# CPU.net
KiCad netlist of a schematic drawn in Altium Designer
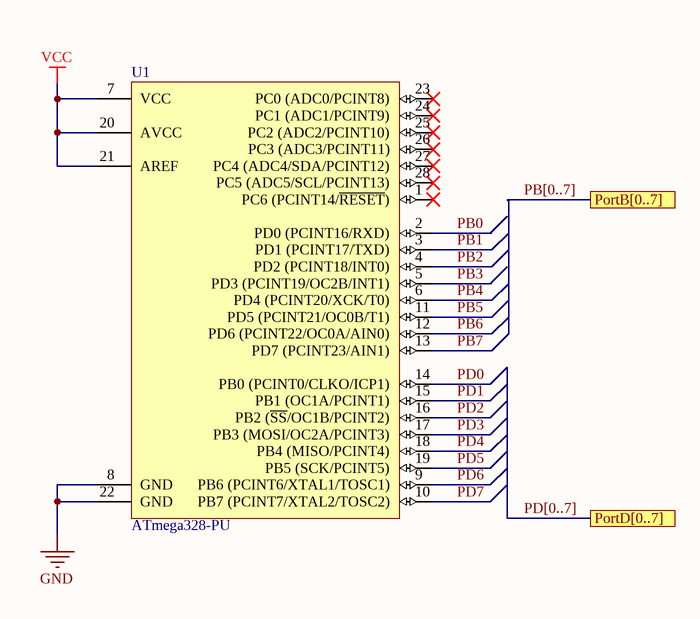
[diagram p0: CPU.SchDoc]

(export (version "E")
  (design (tool "Eeschema 10.0.6"))
  (components
    (comp (ref "U1")
      (value "ATmega328-PU")
      (footprint "28P3")
      (libsource (lib "Altium Content Vault") (part "MC-8B-ATM48-IL28"))
    )
  )
  (nets
    (net (code "1") (name "/PB0") (class "Default")
      (node (ref "U1") (pin "2") (pinfunction "PD0_(PCINT16/RXD)_2") (pintype "bidirectional"))
    )
    (net (code "2") (name "/PB1") (class "Default")
      (node (ref "U1") (pin "3") (pinfunction "PD1_(PCINT17/TXD)_3") (pintype "bidirectional"))
    )
    (net (code "3") (name "/PB2") (class "Default")
      (node (ref "U1") (pin "4") (pinfunction "PD2_(PCINT18/INT0)_4") (pintype "bidirectional"))
    )
    (net (code "4") (name "/PB3") (class "Default")
      (node (ref "U1") (pin "5") (pinfunction "PD3_(PCINT19/OC2B/INT1)_5") (pintype "bidirectional"))
    )
    (net (code "5") (name "/PB4") (class "Default")
      (node (ref "U1") (pin "6") (pinfunction "PD4_(PCINT20/XCK/T0)_6") (pintype "bidirectional"))
    )
    (net (code "6") (name "/PB5") (class "Default")
      (node (ref "U1") (pin "11") (pinfunction "PD5_(PCINT21/OC0B/T1)_11") (pintype "bidirectional"))
    )
    (net (code "7") (name "/PB6") (class "Default")
      (node (ref "U1") (pin "12") (pinfunction "PD6_(PCINT22/OC0A/AIN0)_12") (pintype "bidirectional"))
    )
    (net (code "8") (name "/PB7") (class "Default")
      (node (ref "U1") (pin "13") (pinfunction "PD7_(PCINT23/AIN1)_13") (pintype "bidirectional"))
    )
    (net (code "10") (name "/PD0") (class "Default")
      (node (ref "U1") (pin "14") (pinfunction "PB0_(PCINT0/CLKO/ICP1)_14") (pintype "bidirectional"))
    )
    (net (code "11") (name "/PD1") (class "Default")
      (node (ref "U1") (pin "15") (pinfunction "PB1_(OC1A/PCINT1)_15") (pintype "bidirectional"))
    )
    (net (code "12") (name "/PD2") (class "Default")
      (node (ref "U1") (pin "16") (pinfunction "PB2_(~{SS}/OC1B/PCINT2)_16") (pintype "bidirectional"))
    )
    (net (code "13") (name "/PD3") (class "Default")
      (node (ref "U1") (pin "17") (pinfunction "PB3_(MOSI/OC2A/PCINT3)_17") (pintype "bidirectional"))
    )
    (net (code "14") (name "/PD4") (class "Default")
      (node (ref "U1") (pin "18") (pinfunction "PB4_(MISO/PCINT4)_18") (pintype "bidirectional"))
    )
    (net (code "15") (name "/PD5") (class "Default")
      (node (ref "U1") (pin "19") (pinfunction "PB5_(SCK/PCINT5)_19") (pintype "bidirectional"))
    )
    (net (code "16") (name "/PD6") (class "Default")
      (node (ref "U1") (pin "9") (pinfunction "PB6_(PCINT6/XTAL1/TOSC1)_9") (pintype "bidirectional"))
    )
    (net (code "17") (name "/PD7") (class "Default")
      (node (ref "U1") (pin "10") (pinfunction "PB7_(PCINT7/XTAL2/TOSC2)_10") (pintype "bidirectional"))
    )
    (net (code "19") (name "GND") (class "Default")
      (node (ref "U1") (pin "22") (pinfunction "GND_22") (pintype "power_in"))
      (node (ref "U1") (pin "8") (pinfunction "GND_8") (pintype "power_in"))
    )
    (net (code "20") (name "VCC") (class "Default")
      (node (ref "U1") (pin "20") (pinfunction "AVCC_20") (pintype "power_in"))
      (node (ref "U1") (pin "21") (pinfunction "AREF_21") (pintype "power_in"))
      (node (ref "U1") (pin "7") (pinfunction "VCC_7") (pintype "power_in"))
    )
    (net (code "21") (name "unconnected-(U1-PC0_(ADC0{slash}PCINT8)-Pad23)") (class "Default")
      (node (ref "U1") (pin "23") (pinfunction "PC0_(ADC0/PCINT8)_23") (pintype "bidirectional+no_connect"))
    )
    (net (code "22") (name "unconnected-(U1-PC1_(ADC1{slash}PCINT9)-Pad24)") (class "Default")
      (node (ref "U1") (pin "24") (pinfunction "PC1_(ADC1/PCINT9)_24") (pintype "bidirectional+no_connect"))
    )
    (net (code "23") (name "unconnected-(U1-PC2_(ADC2{slash}PCINT10)-Pad25)") (class "Default")
      (node (ref "U1") (pin "25") (pinfunction "PC2_(ADC2/PCINT10)_25") (pintype "bidirectional+no_connect"))
    )
    (net (code "24") (name "unconnected-(U1-PC3_(ADC3{slash}PCINT11)-Pad26)") (class "Default")
      (node (ref "U1") (pin "26") (pinfunction "PC3_(ADC3/PCINT11)_26") (pintype "bidirectional+no_connect"))
    )
    (net (code "25") (name "unconnected-(U1-PC4_(ADC4{slash}SDA{slash}PCINT12)-Pad27)") (class "Default")
      (node (ref "U1") (pin "27") (pinfunction "PC4_(ADC4/SDA/PCINT12)_27") (pintype "bidirectional+no_connect"))
    )
    (net (code "26") (name "unconnected-(U1-PC5_(ADC5{slash}SCL{slash}PCINT13)-Pad28)") (class "Default")
      (node (ref "U1") (pin "28") (pinfunction "PC5_(ADC5/SCL/PCINT13)_28") (pintype "bidirectional+no_connect"))
    )
    (net (code "27") (name "unconnected-(U1-PC6_(PCINT14{slash}~{RESET})-Pad1)") (class "Default")
      (node (ref "U1") (pin "1") (pinfunction "PC6_(PCINT14/~{RESET})_1") (pintype "bidirectional+no_connect"))
    )
  )
)
